# ESP32-WROOM-32.net
KiCad netlist of a schematic drawn in Altium Designer
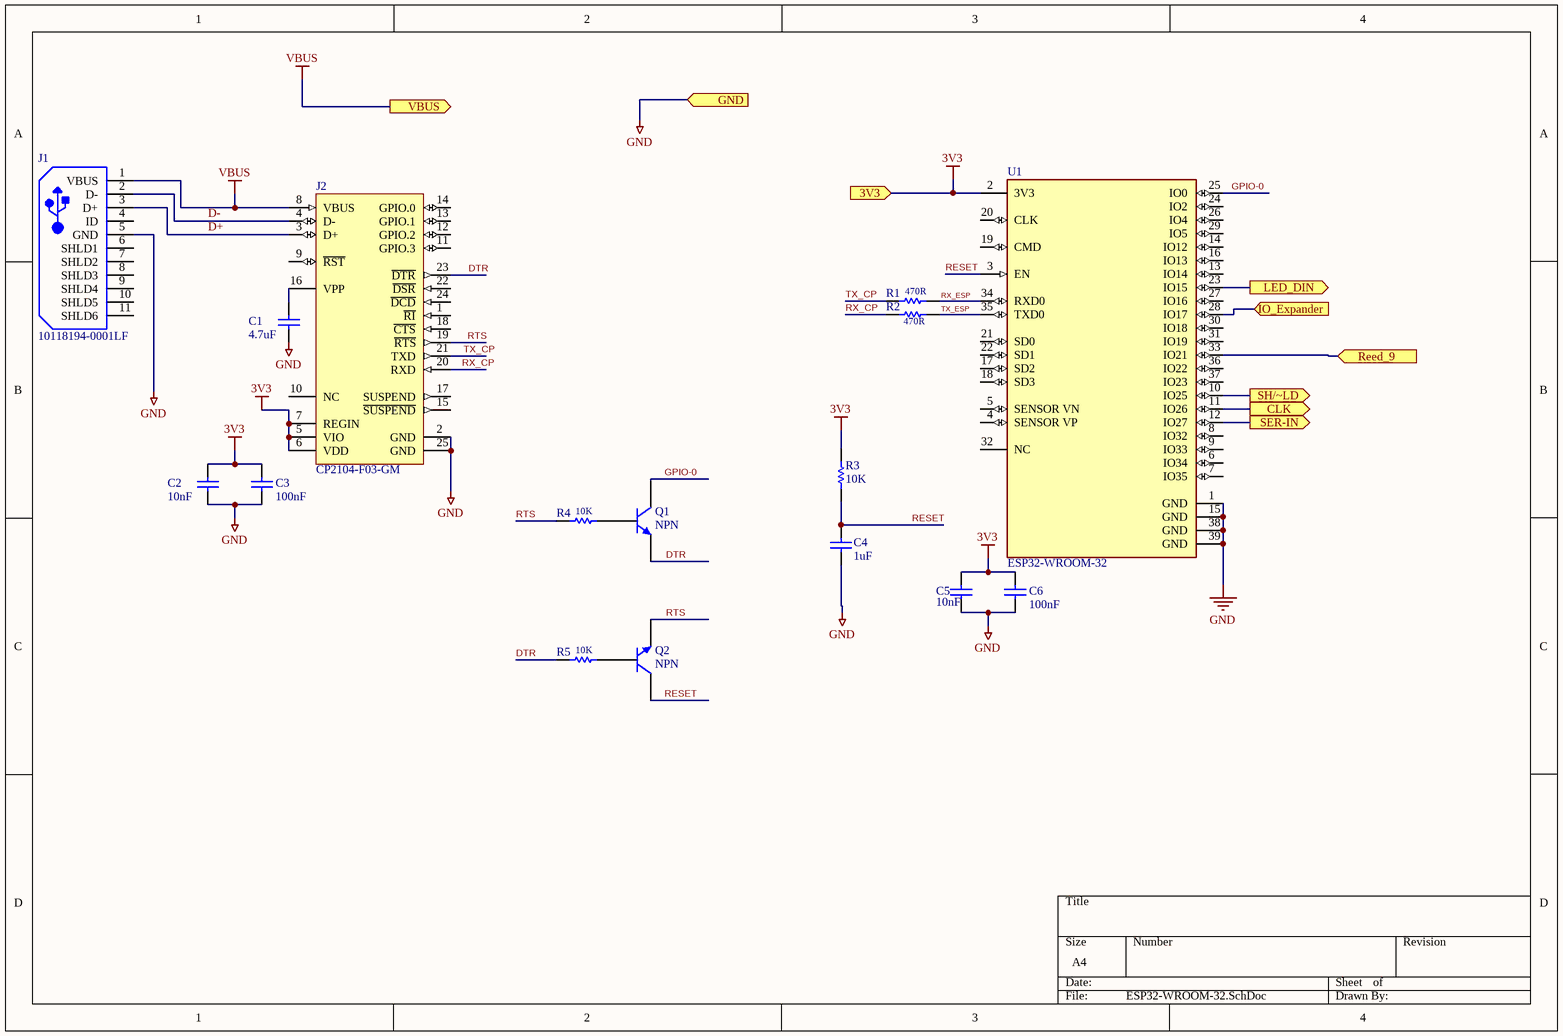
[diagram p0: ESP32-WROOM-32.SchDoc]

(export (version "E")
  (design (tool "Eeschema 10.0.6"))
  (components
    (comp (ref "C1")
      (value "4.7uF")
      (footprint "CAPC1608X90X20LL10")
      (description "Chip Capacitor, 0.1 uF, +/- 10%, 50 V, -55 to 125 degC, 0603 (1608 Metric), RoHS, Tape and Reel")
      (fields (field (name "VOLTAGE") "50V") (field (name "TOLERANCE") "10%"))
      (libsource (lib "Altium Content Vault") (part "CAP-NP-2"))
    )
    (comp (ref "C2")
      (value "10nF")
      (footprint "CAPC1608X90X20LL10")
      (description "Chip Capacitor, 0.1 uF, +/- 10%, 50 V, -55 to 125 degC, 0603 (1608 Metric), RoHS, Tape and Reel")
      (fields (field (name "VOLTAGE") "50V") (field (name "TOLERANCE") "10%"))
      (libsource (lib "Altium Content Vault") (part "CAP-NP-2"))
    )
    (comp (ref "C3")
      (value "100nF")
      (footprint "CAPC1608X90X20LL10")
      (description "Chip Capacitor, 0.1 uF, +/- 10%, 50 V, -55 to 125 degC, 0603 (1608 Metric), RoHS, Tape and Reel")
      (fields (field (name "VOLTAGE") "50V") (field (name "TOLERANCE") "10%"))
      (libsource (lib "Altium Content Vault") (part "CAP-NP-2"))
    )
    (comp (ref "C4")
      (value "1uF")
      (footprint "CAPC1608X90X20LL10")
      (description "Chip Capacitor, 0.1 uF, +/- 10%, 50 V, -55 to 125 degC, 0603 (1608 Metric), RoHS, Tape and Reel")
      (fields (field (name "VOLTAGE") "50V") (field (name "TOLERANCE") "10%"))
      (libsource (lib "Altium Content Vault") (part "CAP-NP-2"))
    )
    (comp (ref "C5")
      (value "10nF")
      (footprint "CAPC1608X90X20LL10")
      (description "Chip Capacitor, 0.1 uF, +/- 10%, 50 V, -55 to 125 degC, 0603 (1608 Metric), RoHS, Tape and Reel")
      (fields (field (name "VOLTAGE") "50V") (field (name "TOLERANCE") "10%"))
      (libsource (lib "Altium Content Vault") (part "CAP-NP-2"))
    )
    (comp (ref "C6")
      (value "100nF")
      (footprint "CAPC1608X90X20LL10")
      (description "Chip Capacitor, 0.1 uF, +/- 10%, 50 V, -55 to 125 degC, 0603 (1608 Metric), RoHS, Tape and Reel")
      (fields (field (name "VOLTAGE") "50V") (field (name "TOLERANCE") "10%"))
      (libsource (lib "Altium Content Vault") (part "CAP-NP-2"))
    )
    (comp (ref "J1")
      (value "10118194-0001LF")
      (footprint "FCI-10118194-0001LF-5_V")
      (description "Micro USB B Type Receptacle, 1.8 A, -55 to 85 degC, 5-Pin SMD, RoHS, Tape and Reel")
      (fields (field (name "MANUFACTURER") "Amphenol FCI"))
      (libsource (lib "Altium Content Vault") (part "USB-5-6SHLD"))
    )
    (comp (ref "J2")
      (value "CP2104-F03-GM")
      (footprint "SLAB-QFN-24-2675x2675TP_M")
      (fields (field (name "MANUFACTURER") "Silicon Labs"))
      (libsource (lib "Altium Content Vault") (part "SLAB-CP2104-QFN-24-25"))
    )
    (comp (ref "Q1")
      (value "NPN")
      (footprint "SOT23_N")
      (description "NPN Bipolar Transistor")
      (fields (field (name "PUBLISHER") "Altium Limited"))
      (libsource (lib "Miscellaneous Devices") (part "NPN"))
    )
    (comp (ref "Q2")
      (value "NPN")
      (footprint "SOT23_N")
      (description "NPN Bipolar Transistor")
      (fields (field (name "PUBLISHER") "Altium Limited"))
      (libsource (lib "Miscellaneous Devices") (part "NPN"))
    )
    (comp (ref "R1")
      (value "470R")
      (footprint "RESC1608X55X25LL10T15")
      (libsource (lib "Altium Content Vault") (part "RES-2"))
    )
    (comp (ref "R2")
      (value "470R")
      (footprint "RESC1608X55X25LL10T15")
      (libsource (lib "Altium Content Vault") (part "RES-2"))
    )
    (comp (ref "R3")
      (value "10K")
      (footprint "RESC1608X55X25LL10T15")
      (libsource (lib "Altium Content Vault") (part "RES-2"))
    )
    (comp (ref "R4")
      (value "10K")
      (footprint "RESC1608X55X25LL10T15")
      (libsource (lib "Altium Content Vault") (part "RES-2"))
    )
    (comp (ref "R5")
      (value "10K")
      (footprint "RESC1608X55X25LL10T15")
      (libsource (lib "Altium Content Vault") (part "RES-2"))
    )
    (comp (ref "U1")
      (value "ESP32-WROOM-32")
      (footprint "FP-ESP32-WROOM-32-MFG")
      (description "RX TXRX MOD WIFI SURFACE MOUNT")
      (libsource (lib "Altium Content Vault") (part "ee866abf0b6c51247b7f5cdebf2f250"))
    )
  )
  (nets
    (net (code "1") (name "/CLK") (class "Default")
      (node (ref "U1") (pin "11") (pinfunction "IO26_11") (pintype "bidirectional"))
    )
    (net (code "2") (name "/D+") (class "Default")
      (node (ref "J1") (pin "3") (pinfunction "D+_3") (pintype "passive"))
      (node (ref "J2") (pin "3") (pinfunction "D+_3") (pintype "bidirectional"))
    )
    (net (code "3") (name "/D-") (class "Default")
      (node (ref "J1") (pin "2") (pinfunction "D-_2") (pintype "passive"))
      (node (ref "J2") (pin "4") (pinfunction "D-_4") (pintype "bidirectional"))
    )
    (net (code "4") (name "/DTR") (class "Default")
      (node (ref "J2") (pin "23") (pinfunction "~{DTR}_23") (pintype "output"))
      (node (ref "Q1") (pin "3") (pinfunction "E_3") (pintype "passive"))
      (node (ref "R5") (pin "2") (pinfunction "2_2") (pintype "passive"))
    )
    (net (code "5") (name "/GPIO-0") (class "Default")
      (node (ref "Q1") (pin "1") (pinfunction "C_1") (pintype "passive"))
      (node (ref "U1") (pin "25") (pinfunction "IO0_25") (pintype "bidirectional"))
    )
    (net (code "6") (name "/IO_Expander") (class "Default")
      (node (ref "U1") (pin "28") (pinfunction "IO17_28") (pintype "bidirectional"))
    )
    (net (code "7") (name "/LED_DIN") (class "Default")
      (node (ref "U1") (pin "23") (pinfunction "IO15_23") (pintype "bidirectional"))
    )
    (net (code "8") (name "/RESET") (class "Default")
      (node (ref "C4") (pin "2") (pinfunction "2_2") (pintype "passive"))
      (node (ref "Q2") (pin "1") (pinfunction "C_1") (pintype "passive"))
      (node (ref "R3") (pin "1") (pinfunction "1_1") (pintype "passive"))
      (node (ref "U1") (pin "3") (pinfunction "EN_3") (pintype "input"))
    )
    (net (code "9") (name "/RTS") (class "Default")
      (node (ref "J2") (pin "19") (pinfunction "~{RTS}_19") (pintype "output"))
      (node (ref "Q2") (pin "3") (pinfunction "E_3") (pintype "passive"))
      (node (ref "R4") (pin "2") (pinfunction "2_2") (pintype "passive"))
    )
    (net (code "10") (name "/RX_CP") (class "Default")
      (node (ref "J2") (pin "20") (pinfunction "RXD_20") (pintype "input"))
      (node (ref "R2") (pin "2") (pinfunction "2_2") (pintype "passive"))
    )
    (net (code "11") (name "/RX_ESP") (class "Default")
      (node (ref "R1") (pin "1") (pinfunction "1_1") (pintype "passive"))
      (node (ref "U1") (pin "34") (pinfunction "RXD0_34") (pintype "bidirectional"))
    )
    (net (code "12") (name "/Reed_9") (class "Default")
      (node (ref "U1") (pin "33") (pinfunction "IO21_33") (pintype "bidirectional"))
    )
    (net (code "13") (name "/SER-IN") (class "Default")
      (node (ref "U1") (pin "12") (pinfunction "IO27_12") (pintype "bidirectional"))
    )
    (net (code "14") (name "/SH{slash}~LD") (class "Default")
      (node (ref "U1") (pin "10") (pinfunction "IO25_10") (pintype "bidirectional"))
    )
    (net (code "15") (name "/TX_CP") (class "Default")
      (node (ref "J2") (pin "21") (pinfunction "TXD_21") (pintype "output"))
      (node (ref "R1") (pin "2") (pinfunction "2_2") (pintype "passive"))
    )
    (net (code "16") (name "/TX_ESP") (class "Default")
      (node (ref "R2") (pin "1") (pinfunction "1_1") (pintype "passive"))
      (node (ref "U1") (pin "35") (pinfunction "TXD0_35") (pintype "bidirectional"))
    )
    (net (code "17") (name "3V3") (class "Default")
      (node (ref "C2") (pin "2") (pinfunction "2_2") (pintype "passive"))
      (node (ref "C3") (pin "2") (pinfunction "2_2") (pintype "passive"))
      (node (ref "C5") (pin "2") (pinfunction "2_2") (pintype "passive"))
      (node (ref "C6") (pin "2") (pinfunction "2_2") (pintype "passive"))
      (node (ref "J2") (pin "5") (pinfunction "VIO_5") (pintype "power_in"))
      (node (ref "J2") (pin "6") (pinfunction "VDD_6") (pintype "power_in"))
      (node (ref "J2") (pin "7") (pinfunction "REGIN_7") (pintype "power_in"))
      (node (ref "R3") (pin "2") (pinfunction "2_2") (pintype "passive"))
      (node (ref "U1") (pin "2") (pinfunction "3V3_2") (pintype "power_in"))
    )
    (net (code "18") (name "GND") (class "Default")
      (node (ref "C1") (pin "1") (pinfunction "1_1") (pintype "passive"))
      (node (ref "C2") (pin "1") (pinfunction "1_1") (pintype "passive"))
      (node (ref "C3") (pin "1") (pinfunction "1_1") (pintype "passive"))
      (node (ref "C4") (pin "1") (pinfunction "1_1") (pintype "passive"))
      (node (ref "C5") (pin "1") (pinfunction "1_1") (pintype "passive"))
      (node (ref "C6") (pin "1") (pinfunction "1_1") (pintype "passive"))
      (node (ref "J1") (pin "5") (pinfunction "GND_5") (pintype "passive"))
      (node (ref "J2") (pin "2") (pinfunction "GND_2") (pintype "power_in"))
      (node (ref "J2") (pin "25") (pinfunction "GND_25") (pintype "power_in"))
      (node (ref "U1") (pin "1") (pinfunction "GND_1") (pintype "power_in"))
      (node (ref "U1") (pin "15") (pinfunction "GND_15") (pintype "power_in"))
      (node (ref "U1") (pin "38") (pinfunction "GND_38") (pintype "power_in"))
      (node (ref "U1") (pin "39") (pinfunction "GND_39") (pintype "power_in"))
    )
    (net (code "19") (name "Net-(J2-VPP)") (class "Default")
      (node (ref "C1") (pin "2") (pinfunction "2_2") (pintype "passive"))
      (node (ref "J2") (pin "16") (pinfunction "VPP_16") (pintype "passive"))
    )
    (net (code "20") (name "Net-(Q1-B)") (class "Default")
      (node (ref "Q1") (pin "2") (pinfunction "B_2") (pintype "passive"))
      (node (ref "R4") (pin "1") (pinfunction "1_1") (pintype "passive"))
    )
    (net (code "21") (name "Net-(Q2-B)") (class "Default")
      (node (ref "Q2") (pin "2") (pinfunction "B_2") (pintype "passive"))
      (node (ref "R5") (pin "1") (pinfunction "1_1") (pintype "passive"))
    )
    (net (code "22") (name "VBUS") (class "Default")
      (node (ref "J1") (pin "1") (pinfunction "VBUS_1") (pintype "passive"))
      (node (ref "J2") (pin "8") (pinfunction "VBUS_8") (pintype "input"))
    )
    (net (code "23") (name "unconnected-(J1-ID-Pad4)") (class "Default")
      (node (ref "J1") (pin "4") (pinfunction "ID_4") (pintype "passive"))
    )
    (net (code "24") (name "unconnected-(J1-SHLD1-Pad6)") (class "Default")
      (node (ref "J1") (pin "6") (pinfunction "SHLD1_6") (pintype "passive"))
    )
    (net (code "25") (name "unconnected-(J1-SHLD2-Pad7)") (class "Default")
      (node (ref "J1") (pin "7") (pinfunction "SHLD2_7") (pintype "passive"))
    )
    (net (code "26") (name "unconnected-(J1-SHLD3-Pad8)") (class "Default")
      (node (ref "J1") (pin "8") (pinfunction "SHLD3_8") (pintype "passive"))
    )
    (net (code "27") (name "unconnected-(J1-SHLD4-Pad9)") (class "Default")
      (node (ref "J1") (pin "9") (pinfunction "SHLD4_9") (pintype "passive"))
    )
    (net (code "28") (name "unconnected-(J1-SHLD5-Pad10)") (class "Default")
      (node (ref "J1") (pin "10") (pinfunction "SHLD5_10") (pintype "passive"))
    )
    (net (code "29") (name "unconnected-(J1-SHLD6-Pad11)") (class "Default")
      (node (ref "J1") (pin "11") (pinfunction "SHLD6_11") (pintype "passive"))
    )
    (net (code "30") (name "unconnected-(J2-GPIO.0-Pad14)") (class "Default")
      (node (ref "J2") (pin "14") (pinfunction "GPIO.0_14") (pintype "bidirectional"))
    )
    (net (code "31") (name "unconnected-(J2-GPIO.1-Pad13)") (class "Default")
      (node (ref "J2") (pin "13") (pinfunction "GPIO.1_13") (pintype "bidirectional"))
    )
    (net (code "32") (name "unconnected-(J2-GPIO.2-Pad12)") (class "Default")
      (node (ref "J2") (pin "12") (pinfunction "GPIO.2_12") (pintype "bidirectional"))
    )
    (net (code "33") (name "unconnected-(J2-GPIO.3-Pad11)") (class "Default")
      (node (ref "J2") (pin "11") (pinfunction "GPIO.3_11") (pintype "bidirectional"))
    )
    (net (code "34") (name "unconnected-(J2-NC-Pad10)") (class "Default")
      (node (ref "J2") (pin "10") (pinfunction "NC_10") (pintype "passive"))
    )
    (net (code "35") (name "unconnected-(J2-SUSPEND-Pad17)") (class "Default")
      (node (ref "J2") (pin "17") (pinfunction "SUSPEND_17") (pintype "output"))
    )
    (net (code "36") (name "unconnected-(J2-~{CTS}-Pad18)") (class "Default")
      (node (ref "J2") (pin "18") (pinfunction "~{CTS}_18") (pintype "input"))
    )
    (net (code "37") (name "unconnected-(J2-~{DCD}-Pad24)") (class "Default")
      (node (ref "J2") (pin "24") (pinfunction "~{DCD}_24") (pintype "input"))
    )
    (net (code "38") (name "unconnected-(J2-~{DSR}-Pad22)") (class "Default")
      (node (ref "J2") (pin "22") (pinfunction "~{DSR}_22") (pintype "input"))
    )
    (net (code "39") (name "unconnected-(J2-~{RI}-Pad1)") (class "Default")
      (node (ref "J2") (pin "1") (pinfunction "~{RI}_1") (pintype "input"))
    )
    (net (code "40") (name "unconnected-(J2-~{RST}-Pad9)") (class "Default")
      (node (ref "J2") (pin "9") (pinfunction "~{RST}_9") (pintype "bidirectional"))
    )
    (net (code "41") (name "unconnected-(J2-~{SUSPEND}-Pad15)") (class "Default")
      (node (ref "J2") (pin "15") (pinfunction "~{SUSPEND}_15") (pintype "output"))
    )
    (net (code "42") (name "unconnected-(U1-CLK-Pad20)") (class "Default")
      (node (ref "U1") (pin "20") (pinfunction "CLK_20") (pintype "bidirectional"))
    )
    (net (code "43") (name "unconnected-(U1-CMD-Pad19)") (class "Default")
      (node (ref "U1") (pin "19") (pinfunction "CMD_19") (pintype "bidirectional"))
    )
    (net (code "44") (name "unconnected-(U1-IO2-Pad24)") (class "Default")
      (node (ref "U1") (pin "24") (pinfunction "IO2_24") (pintype "bidirectional"))
    )
    (net (code "45") (name "unconnected-(U1-IO4-Pad26)") (class "Default")
      (node (ref "U1") (pin "26") (pinfunction "IO4_26") (pintype "bidirectional"))
    )
    (net (code "46") (name "unconnected-(U1-IO5-Pad29)") (class "Default")
      (node (ref "U1") (pin "29") (pinfunction "IO5_29") (pintype "bidirectional"))
    )
    (net (code "47") (name "unconnected-(U1-IO12-Pad14)") (class "Default")
      (node (ref "U1") (pin "14") (pinfunction "IO12_14") (pintype "bidirectional"))
    )
    (net (code "48") (name "unconnected-(U1-IO13-Pad16)") (class "Default")
      (node (ref "U1") (pin "16") (pinfunction "IO13_16") (pintype "bidirectional"))
    )
    (net (code "49") (name "unconnected-(U1-IO14-Pad13)") (class "Default")
      (node (ref "U1") (pin "13") (pinfunction "IO14_13") (pintype "bidirectional"))
    )
    (net (code "50") (name "unconnected-(U1-IO16-Pad27)") (class "Default")
      (node (ref "U1") (pin "27") (pinfunction "IO16_27") (pintype "bidirectional"))
    )
    (net (code "51") (name "unconnected-(U1-IO18-Pad30)") (class "Default")
      (node (ref "U1") (pin "30") (pinfunction "IO18_30") (pintype "bidirectional"))
    )
    (net (code "52") (name "unconnected-(U1-IO19-Pad31)") (class "Default")
      (node (ref "U1") (pin "31") (pinfunction "IO19_31") (pintype "bidirectional"))
    )
    (net (code "53") (name "unconnected-(U1-IO22-Pad36)") (class "Default")
      (node (ref "U1") (pin "36") (pinfunction "IO22_36") (pintype "bidirectional"))
    )
    (net (code "54") (name "unconnected-(U1-IO23-Pad37)") (class "Default")
      (node (ref "U1") (pin "37") (pinfunction "IO23_37") (pintype "bidirectional"))
    )
    (net (code "55") (name "unconnected-(U1-IO32-Pad8)") (class "Default")
      (node (ref "U1") (pin "8") (pinfunction "IO32_8") (pintype "bidirectional"))
    )
    (net (code "56") (name "unconnected-(U1-IO33-Pad9)") (class "Default")
      (node (ref "U1") (pin "9") (pinfunction "IO33_9") (pintype "bidirectional"))
    )
    (net (code "57") (name "unconnected-(U1-IO34-Pad6)") (class "Default")
      (node (ref "U1") (pin "6") (pinfunction "IO34_6") (pintype "bidirectional"))
    )
    (net (code "58") (name "unconnected-(U1-IO35-Pad7)") (class "Default")
      (node (ref "U1") (pin "7") (pinfunction "IO35_7") (pintype "bidirectional"))
    )
    (net (code "59") (name "unconnected-(U1-NC-Pad32)") (class "Default")
      (node (ref "U1") (pin "32") (pinfunction "NC_32") (pintype "passive"))
    )
    (net (code "60") (name "unconnected-(U1-SD0-Pad21)") (class "Default")
      (node (ref "U1") (pin "21") (pinfunction "SD0_21") (pintype "bidirectional"))
    )
    (net (code "61") (name "unconnected-(U1-SD1-Pad22)") (class "Default")
      (node (ref "U1") (pin "22") (pinfunction "SD1_22") (pintype "bidirectional"))
    )
    (net (code "62") (name "unconnected-(U1-SD2-Pad17)") (class "Default")
      (node (ref "U1") (pin "17") (pinfunction "SD2_17") (pintype "bidirectional"))
    )
    (net (code "63") (name "unconnected-(U1-SD3-Pad18)") (class "Default")
      (node (ref "U1") (pin "18") (pinfunction "SD3_18") (pintype "bidirectional"))
    )
    (net (code "64") (name "unconnected-(U1-SENSOR_VN-Pad5)") (class "Default")
      (node (ref "U1") (pin "5") (pinfunction "SENSOR_VN_5") (pintype "bidirectional"))
    )
    (net (code "65") (name "unconnected-(U1-SENSOR_VP-Pad4)") (class "Default")
      (node (ref "U1") (pin "4") (pinfunction "SENSOR_VP_4") (pintype "bidirectional"))
    )
  )
)
